# SCH_USB-Hub_2025-01-17.net
KiCad netlist of a schematic drawn in EasyEDA
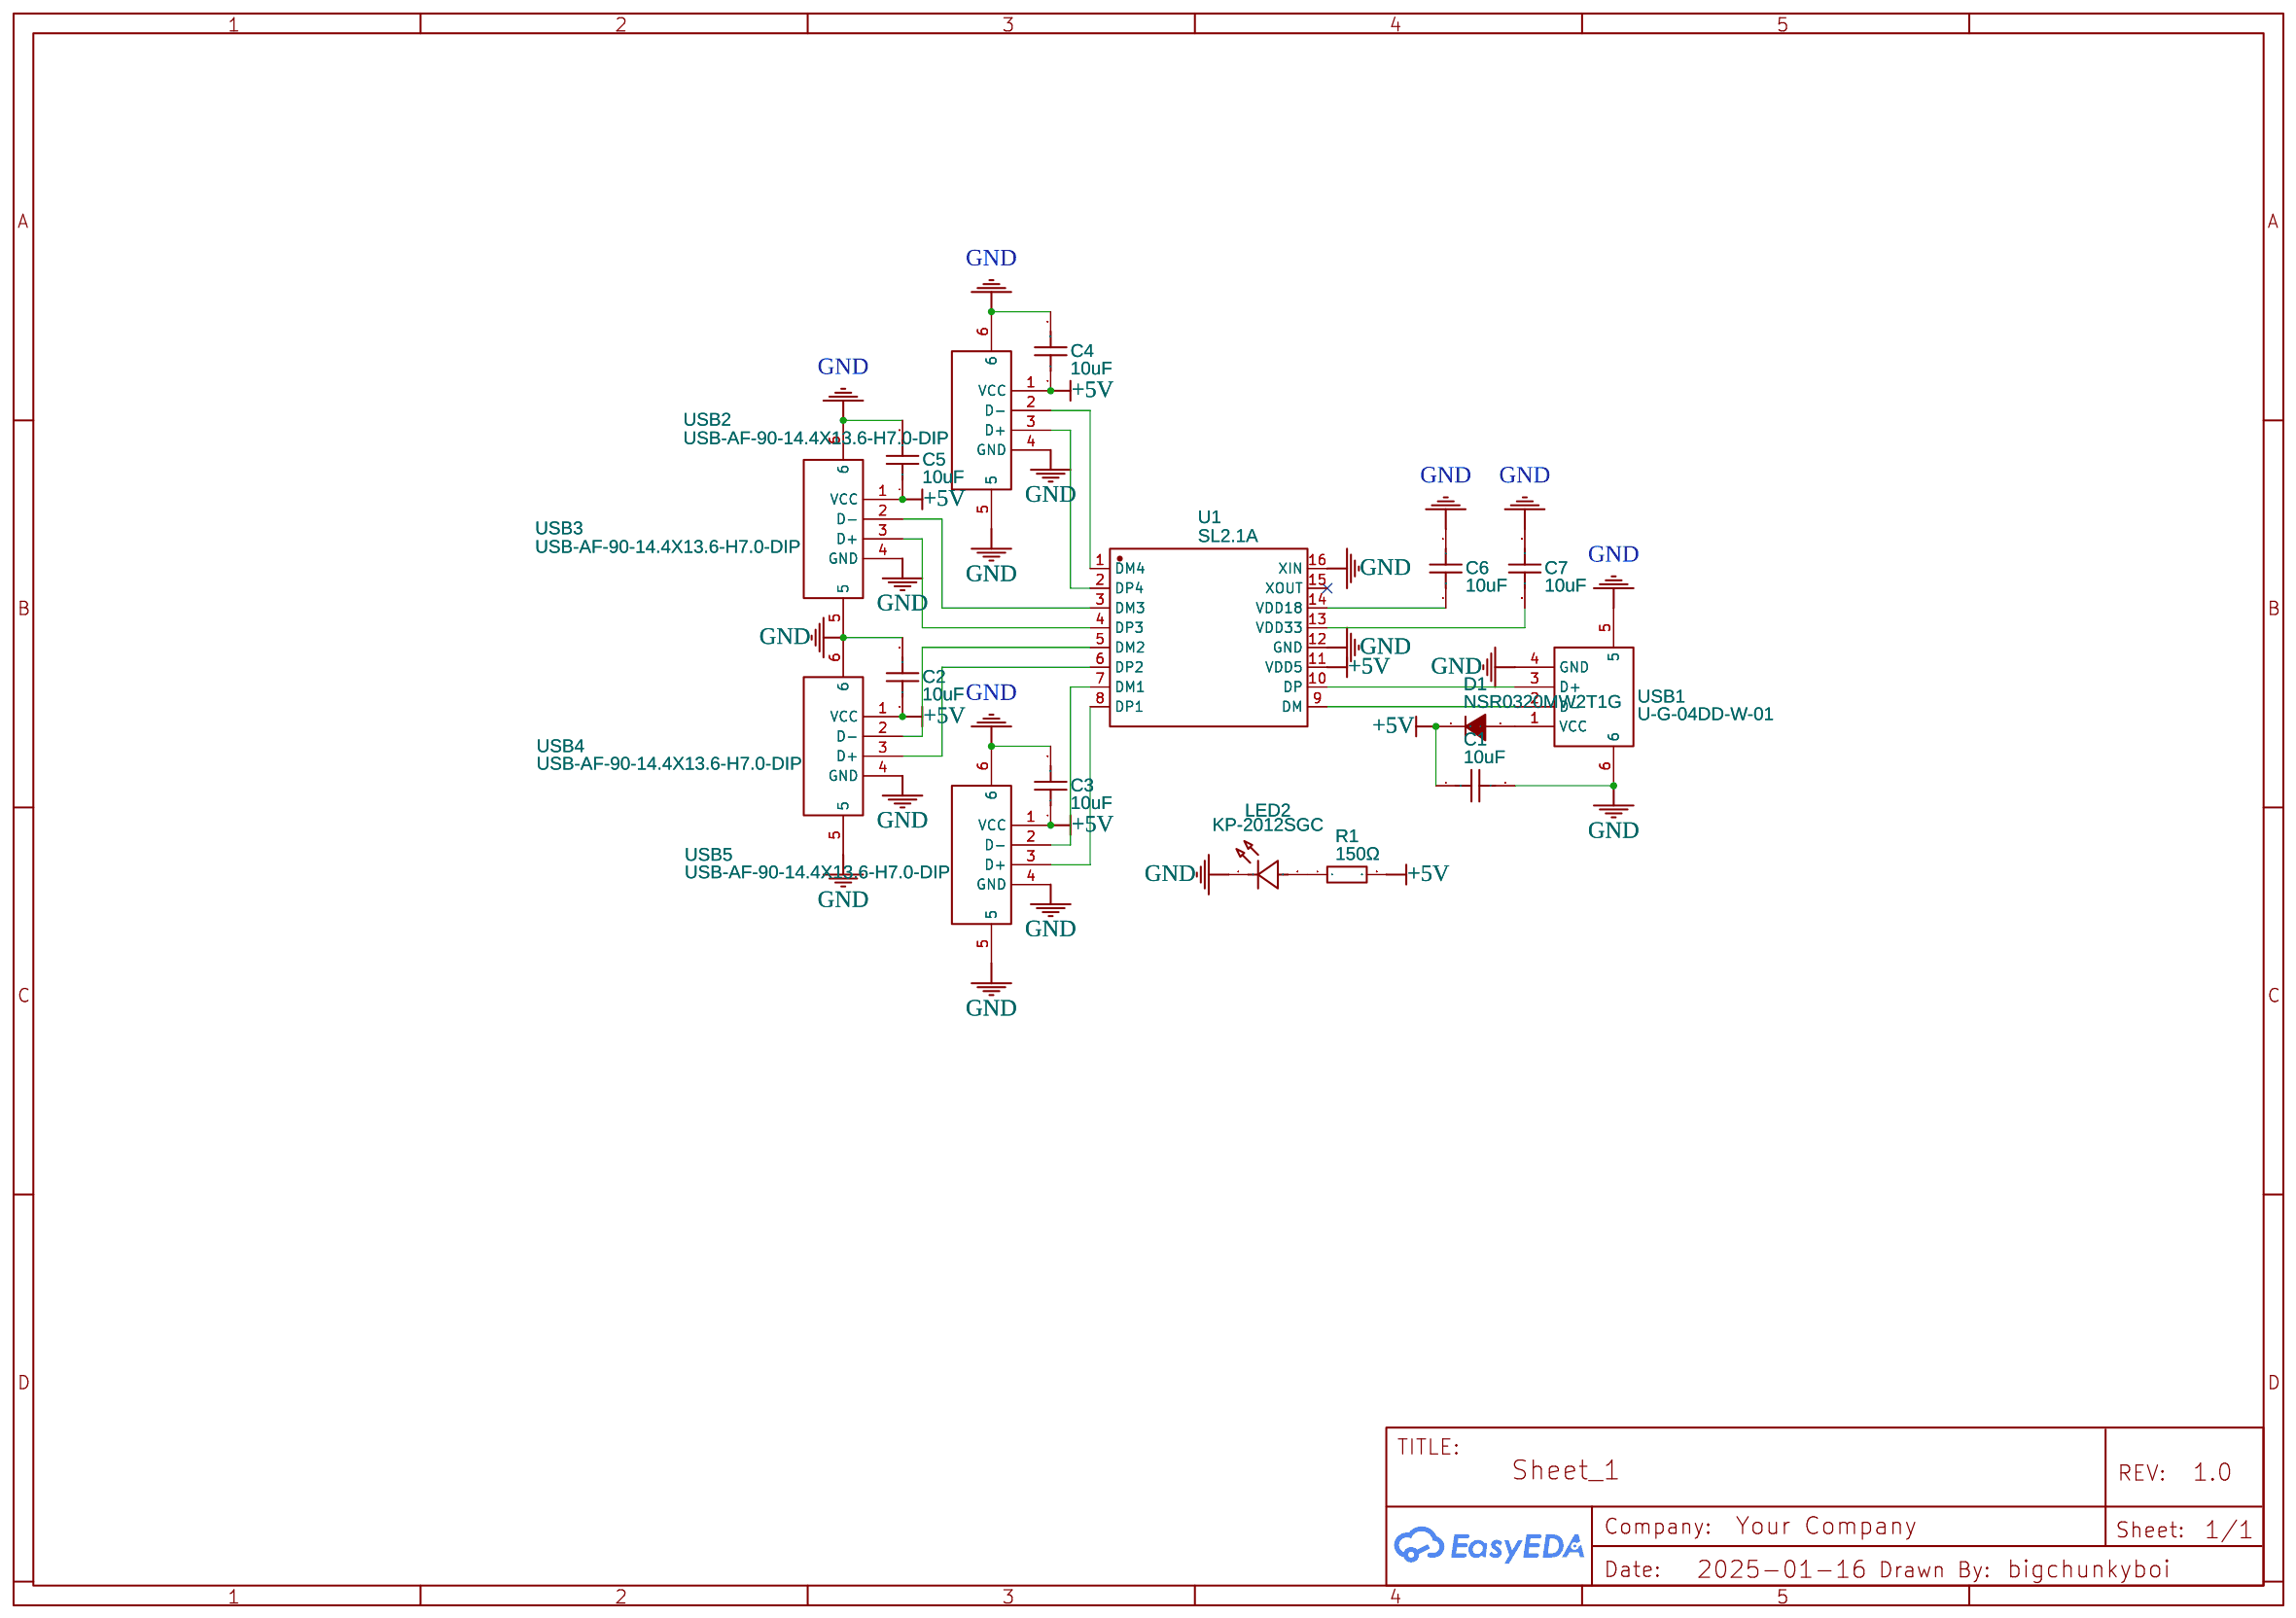
[diagram p0: schematic sheet]

(export (version "E")
  (design (tool "Eeschema 10.0.6"))
  (components
    (comp (ref "C1")
      (value "10uF")
      (fields
        (field (name "Manufacturer Part") "CL10A106KP8NNNC")
        (field (name "Manufacturer") "SAMSUNG(三星)")
      )
      (libsource (lib "") (part "CL10A106KP8NNNC_1"))
    )
    (comp (ref "C2")
      (value "10uF")
      (fields
        (field (name "Manufacturer Part") "CL10A106KP8NNNC")
        (field (name "Manufacturer") "SAMSUNG(三星)")
      )
      (libsource (lib "") (part "CL10A106KP8NNNC"))
    )
    (comp (ref "C3")
      (value "10uF")
      (fields
        (field (name "Manufacturer Part") "CL10A106KP8NNNC")
        (field (name "Manufacturer") "SAMSUNG(三星)")
      )
      (libsource (lib "") (part "CL10A106KP8NNNC"))
    )
    (comp (ref "C4")
      (value "10uF")
      (fields
        (field (name "Manufacturer Part") "CL10A106KP8NNNC")
        (field (name "Manufacturer") "SAMSUNG(三星)")
      )
      (libsource (lib "") (part "CL10A106KP8NNNC"))
    )
    (comp (ref "C5")
      (value "10uF")
      (fields
        (field (name "Manufacturer Part") "CL10A106KP8NNNC")
        (field (name "Manufacturer") "SAMSUNG(三星)")
      )
      (libsource (lib "") (part "CL10A106KP8NNNC"))
    )
    (comp (ref "C6")
      (value "10uF")
      (fields
        (field (name "Manufacturer Part") "CL10A106KP8NNNC")
        (field (name "Manufacturer") "SAMSUNG(三星)")
      )
      (libsource (lib "") (part "CL10A106KP8NNNC_2"))
    )
    (comp (ref "C7")
      (value "10uF")
      (fields
        (field (name "Manufacturer Part") "CL10A106KP8NNNC")
        (field (name "Manufacturer") "SAMSUNG(三星)")
      )
      (libsource (lib "") (part "CL10A106KP8NNNC_2"))
    )
    (comp (ref "D1")
      (value "NSR0320MW2T1G")
      (fields (field (name "Manufacturer") "onsemi(安森美)"))
      (libsource (lib "") (part "NSR0320MW2T1G"))
    )
    (comp (ref "LED2")
      (value "KP-2012SGC")
      (fields (field (name "Manufacturer") "Kingbright"))
      (libsource (lib "") (part "KP-2012SGC"))
    )
    (comp (ref "R1")
      (value "150Ω")
      (fields (field (name "Manufacturer Part") "RC0603FR-07150RL") (field (name "Manufacturer") "YAGEO(国巨)"))
      (libsource (lib "") (part "RC0603FR-07150RL"))
    )
    (comp (ref "U1")
      (value "SL2.1A")
      (fields (field (name "Manufacturer") "CoreChips(和芯润德)"))
      (libsource (lib "") (part "SL2.1A"))
    )
    (comp (ref "USB1")
      (value "U-G-04DD-W-01")
      (fields (field (name "Manufacturer Part") "U-G-O4DD-W-1") (field (name "Manufacturer") "韩国韩荣"))
      (libsource (lib "") (part "U-G-04DD-W-01"))
    )
    (comp (ref "USB2")
      (value "USB-AF-90-14.4X13.6-H7.0-DIP")
      (fields (field (name "Manufacturer Part") "903-131A1011D10100") (field (name "Manufacturer") "精拓金"))
      (libsource (lib "") (part "USB-AF-90-14.4X13.6-H7.0-DIP"))
    )
    (comp (ref "USB3")
      (value "USB-AF-90-14.4X13.6-H7.0-DIP")
      (fields (field (name "Manufacturer Part") "903-131A1011D10100") (field (name "Manufacturer") "精拓金"))
      (libsource (lib "") (part "USB-AF-90-14.4X13.6-H7.0-DIP"))
    )
    (comp (ref "USB4")
      (value "USB-AF-90-14.4X13.6-H7.0-DIP")
      (fields (field (name "Manufacturer Part") "903-131A1011D10100") (field (name "Manufacturer") "精拓金"))
      (libsource (lib "") (part "USB-AF-90-14.4X13.6-H7.0-DIP"))
    )
    (comp (ref "USB5")
      (value "USB-AF-90-14.4X13.6-H7.0-DIP")
      (fields (field (name "Manufacturer Part") "903-131A1011D10100") (field (name "Manufacturer") "精拓金"))
      (libsource (lib "") (part "USB-AF-90-14.4X13.6-H7.0-DIP"))
    )
  )
  (nets
    (net (code "1") (name "+5V") (class "Default")
      (node (ref "C1") (pin "1") (pinfunction "1_1") (pintype "unspecified"))
      (node (ref "C2") (pin "1") (pinfunction "1_1") (pintype "unspecified"))
      (node (ref "C3") (pin "1") (pinfunction "1_1") (pintype "unspecified"))
      (node (ref "C4") (pin "1") (pinfunction "1_1") (pintype "unspecified"))
      (node (ref "C5") (pin "1") (pinfunction "1_1") (pintype "unspecified"))
      (node (ref "D1") (pin "1") (pinfunction "C_1") (pintype "unspecified"))
      (node (ref "R1") (pin "2") (pinfunction "2_2") (pintype "input"))
      (node (ref "U1") (pin "11") (pinfunction "VDD5_11") (pintype "unspecified"))
      (node (ref "USB2") (pin "1") (pinfunction "VCC_1") (pintype "unspecified"))
      (node (ref "USB3") (pin "1") (pinfunction "VCC_1") (pintype "unspecified"))
      (node (ref "USB4") (pin "1") (pinfunction "VCC_1") (pintype "unspecified"))
      (node (ref "USB5") (pin "1") (pinfunction "VCC_1") (pintype "unspecified"))
    )
    (net (code "2") (name "GND") (class "Default")
      (node (ref "C1") (pin "2") (pinfunction "2_2") (pintype "unspecified"))
      (node (ref "C2") (pin "2") (pinfunction "2_2") (pintype "unspecified"))
      (node (ref "C3") (pin "2") (pinfunction "2_2") (pintype "unspecified"))
      (node (ref "C4") (pin "2") (pinfunction "2_2") (pintype "unspecified"))
      (node (ref "C5") (pin "2") (pinfunction "2_2") (pintype "unspecified"))
      (node (ref "C6") (pin "1") (pinfunction "1_1") (pintype "unspecified"))
      (node (ref "C7") (pin "1") (pinfunction "1_1") (pintype "unspecified"))
      (node (ref "LED2") (pin "1") (pinfunction "K_1") (pintype "unspecified"))
      (node (ref "U1") (pin "12") (pinfunction "GND_12") (pintype "unspecified"))
      (node (ref "U1") (pin "16") (pinfunction "XIN_16") (pintype "unspecified"))
      (node (ref "USB1") (pin "4") (pinfunction "GND_4") (pintype "unspecified"))
      (node (ref "USB1") (pin "5") (pinfunction "5_5") (pintype "unspecified"))
      (node (ref "USB1") (pin "6") (pinfunction "6_6") (pintype "unspecified"))
      (node (ref "USB2") (pin "4") (pinfunction "GND_4") (pintype "unspecified"))
      (node (ref "USB2") (pin "5") (pinfunction "5_5") (pintype "unspecified"))
      (node (ref "USB2") (pin "6") (pinfunction "6_6") (pintype "unspecified"))
      (node (ref "USB3") (pin "4") (pinfunction "GND_4") (pintype "unspecified"))
      (node (ref "USB3") (pin "5") (pinfunction "5_5") (pintype "unspecified"))
      (node (ref "USB3") (pin "6") (pinfunction "6_6") (pintype "unspecified"))
      (node (ref "USB4") (pin "4") (pinfunction "GND_4") (pintype "unspecified"))
      (node (ref "USB4") (pin "5") (pinfunction "5_5") (pintype "unspecified"))
      (node (ref "USB4") (pin "6") (pinfunction "6_6") (pintype "unspecified"))
      (node (ref "USB5") (pin "4") (pinfunction "GND_4") (pintype "unspecified"))
      (node (ref "USB5") (pin "5") (pinfunction "5_5") (pintype "unspecified"))
      (node (ref "USB5") (pin "6") (pinfunction "6_6") (pintype "unspecified"))
    )
    (net (code "3") (name "Net-(D1-A)") (class "Default")
      (node (ref "D1") (pin "2") (pinfunction "A_2") (pintype "unspecified"))
      (node (ref "USB1") (pin "1") (pinfunction "VCC_1") (pintype "unspecified"))
    )
    (net (code "4") (name "Net-(LED2-A)") (class "Default")
      (node (ref "LED2") (pin "2") (pinfunction "A_2") (pintype "unspecified"))
      (node (ref "R1") (pin "1") (pinfunction "1_1") (pintype "input"))
    )
    (net (code "5") (name "Net-(U1-DM)") (class "Default")
      (node (ref "U1") (pin "9") (pinfunction "DM_9") (pintype "unspecified"))
      (node (ref "USB1") (pin "2") (pinfunction "D-_2") (pintype "unspecified"))
    )
    (net (code "6") (name "Net-(U1-DM1)") (class "Default")
      (node (ref "U1") (pin "7") (pinfunction "DM1_7") (pintype "unspecified"))
      (node (ref "USB5") (pin "2") (pinfunction "D-_2") (pintype "unspecified"))
    )
    (net (code "7") (name "Net-(U1-DM2)") (class "Default")
      (node (ref "U1") (pin "5") (pinfunction "DM2_5") (pintype "unspecified"))
      (node (ref "USB4") (pin "2") (pinfunction "D-_2") (pintype "unspecified"))
    )
    (net (code "8") (name "Net-(U1-DM3)") (class "Default")
      (node (ref "U1") (pin "3") (pinfunction "DM3_3") (pintype "unspecified"))
      (node (ref "USB3") (pin "2") (pinfunction "D-_2") (pintype "unspecified"))
    )
    (net (code "9") (name "Net-(U1-DM4)") (class "Default")
      (node (ref "U1") (pin "1") (pinfunction "DM4_1") (pintype "unspecified"))
      (node (ref "USB2") (pin "2") (pinfunction "D-_2") (pintype "unspecified"))
    )
    (net (code "10") (name "Net-(U1-DP)") (class "Default")
      (node (ref "U1") (pin "10") (pinfunction "DP_10") (pintype "unspecified"))
      (node (ref "USB1") (pin "3") (pinfunction "D+_3") (pintype "unspecified"))
    )
    (net (code "11") (name "Net-(U1-DP1)") (class "Default")
      (node (ref "U1") (pin "8") (pinfunction "DP1_8") (pintype "unspecified"))
      (node (ref "USB5") (pin "3") (pinfunction "D+_3") (pintype "unspecified"))
    )
    (net (code "12") (name "Net-(U1-DP2)") (class "Default")
      (node (ref "U1") (pin "6") (pinfunction "DP2_6") (pintype "unspecified"))
      (node (ref "USB4") (pin "3") (pinfunction "D+_3") (pintype "unspecified"))
    )
    (net (code "13") (name "Net-(U1-DP3)") (class "Default")
      (node (ref "U1") (pin "4") (pinfunction "DP3_4") (pintype "unspecified"))
      (node (ref "USB3") (pin "3") (pinfunction "D+_3") (pintype "unspecified"))
    )
    (net (code "14") (name "Net-(U1-DP4)") (class "Default")
      (node (ref "U1") (pin "2") (pinfunction "DP4_2") (pintype "unspecified"))
      (node (ref "USB2") (pin "3") (pinfunction "D+_3") (pintype "unspecified"))
    )
    (net (code "15") (name "Net-(U1-VDD18)") (class "Default")
      (node (ref "C6") (pin "2") (pinfunction "2_2") (pintype "unspecified"))
      (node (ref "U1") (pin "14") (pinfunction "VDD18_14") (pintype "unspecified"))
    )
    (net (code "16") (name "Net-(U1-VDD33)") (class "Default")
      (node (ref "C7") (pin "2") (pinfunction "2_2") (pintype "unspecified"))
      (node (ref "U1") (pin "13") (pinfunction "VDD33_13") (pintype "unspecified"))
    )
    (net (code "17") (name "unconnected-(U1-XOUT-Pad15)") (class "Default")
      (node (ref "U1") (pin "15") (pinfunction "XOUT_15") (pintype "unspecified+no_connect"))
    )
  )
)
